# esp8266kotak.net
KiCad netlist of a schematic drawn in EAGLE
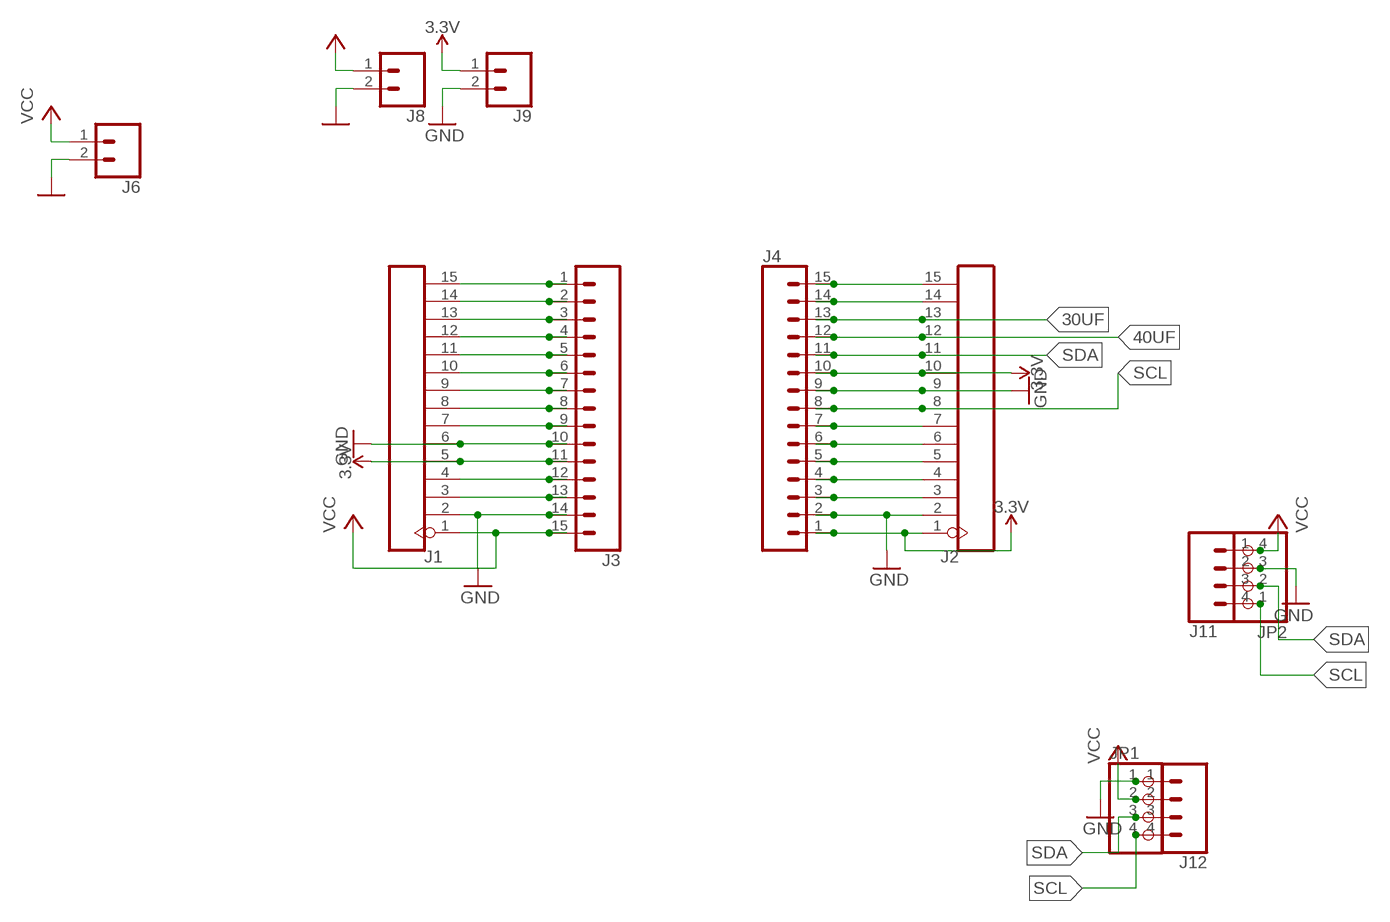
[diagram p0: schematic, sheet 1]

(export (version "E")
  (design (tool "Eeschema 10.0.6"))
  (components
    (comp (ref "J1")
      (value "HEADER-15P2.54")
      (footprint "eagle-import:15P-2.54")
      (libsource (lib "eagle-import") (part "HEADER-15P2.54"))
    )
    (comp (ref "J2")
      (value "HEADER-15P2.54")
      (footprint "eagle-import:15P-2.54")
      (libsource (lib "eagle-import") (part "HEADER-15P2.54"))
    )
    (comp (ref "J3")
      (value "CONN_15")
      (footprint "eagle-import:1X15")
      (libsource (lib "eagle-import") (part "CONN_15"))
    )
    (comp (ref "J4")
      (value "CONN_15")
      (footprint "eagle-import:1X15")
      (libsource (lib "eagle-import") (part "CONN_15"))
    )
    (comp (ref "J6")
      (value "CONN_02")
      (footprint "eagle-import:1X02")
      (libsource (lib "eagle-import") (part "CONN_02"))
    )
    (comp (ref "J8")
      (value "CONN_02")
      (footprint "eagle-import:1X02")
      (libsource (lib "eagle-import") (part "CONN_02"))
    )
    (comp (ref "J9")
      (value "CONN_02")
      (footprint "eagle-import:1X02")
      (libsource (lib "eagle-import") (part "CONN_02"))
    )
    (comp (ref "J11")
      (value "CONN_04")
      (footprint "eagle-import:1X04")
      (libsource (lib "eagle-import") (part "CONN_04"))
    )
    (comp (ref "J12")
      (value "CONN_04")
      (footprint "eagle-import:1X04")
      (libsource (lib "eagle-import") (part "CONN_04"))
    )
    (comp (ref "JP1")
      (value "PINHD-1X4/90")
      (footprint "eagle-import:1X04_90")
      (libsource (lib "eagle-import") (part "PINHD-1X4/90"))
    )
    (comp (ref "JP2")
      (value "PINHD-1X4/90")
      (footprint "eagle-import:1X04_90")
      (libsource (lib "eagle-import") (part "PINHD-1X4/90"))
    )
  )
  (nets
    (net (code "1") (name "3.3V") (class "Default")
      (node (ref "J1") (pin "5") (pinfunction "5_5") (pintype "passive"))
      (node (ref "J2") (pin "1") (pinfunction "1_1") (pintype "passive"))
      (node (ref "J2") (pin "10") (pinfunction "10_10") (pintype "passive"))
      (node (ref "J3") (pin "11") (pinfunction "11_11") (pintype "passive"))
      (node (ref "J4") (pin "1") (pinfunction "1_1") (pintype "passive"))
      (node (ref "J4") (pin "10") (pinfunction "10_10") (pintype "passive"))
      (node (ref "J9") (pin "1") (pinfunction "1_1") (pintype "passive"))
    )
    (net (code "2") (name "30UF") (class "Default")
      (node (ref "J2") (pin "13") (pinfunction "13_13") (pintype "passive"))
      (node (ref "J4") (pin "13") (pinfunction "13_13") (pintype "passive"))
    )
    (net (code "3") (name "40UF") (class "Default")
      (node (ref "J2") (pin "12") (pinfunction "12_12") (pintype "passive"))
      (node (ref "J4") (pin "12") (pinfunction "12_12") (pintype "passive"))
    )
    (net (code "4") (name "GND") (class "Default")
      (node (ref "J1") (pin "2") (pinfunction "2_2") (pintype "passive"))
      (node (ref "J1") (pin "6") (pinfunction "6_6") (pintype "passive"))
      (node (ref "J11") (pin "2") (pinfunction "2_2") (pintype "passive"))
      (node (ref "J12") (pin "1") (pinfunction "1_1") (pintype "passive"))
      (node (ref "J2") (pin "2") (pinfunction "2_2") (pintype "passive"))
      (node (ref "J2") (pin "9") (pinfunction "9_9") (pintype "passive"))
      (node (ref "J3") (pin "10") (pinfunction "10_10") (pintype "passive"))
      (node (ref "J3") (pin "14") (pinfunction "14_14") (pintype "passive"))
      (node (ref "J4") (pin "2") (pinfunction "2_2") (pintype "passive"))
      (node (ref "J4") (pin "9") (pinfunction "9_9") (pintype "passive"))
      (node (ref "J6") (pin "2") (pinfunction "2_2") (pintype "passive"))
      (node (ref "J8") (pin "2") (pinfunction "2_2") (pintype "passive"))
      (node (ref "J9") (pin "2") (pinfunction "2_2") (pintype "passive"))
      (node (ref "JP1") (pin "1") (pinfunction "1_1") (pintype "passive"))
      (node (ref "JP2") (pin "3") (pinfunction "3_3") (pintype "passive"))
    )
    (net (code "5") (name "Net-(J1-Pad3)") (class "Default")
      (node (ref "J1") (pin "3") (pinfunction "3_3") (pintype "passive"))
      (node (ref "J3") (pin "13") (pinfunction "13_13") (pintype "passive"))
    )
    (net (code "6") (name "Net-(J1-Pad4)") (class "Default")
      (node (ref "J1") (pin "4") (pinfunction "4_4") (pintype "passive"))
      (node (ref "J3") (pin "12") (pinfunction "12_12") (pintype "passive"))
    )
    (net (code "7") (name "Net-(J1-Pad7)") (class "Default")
      (node (ref "J1") (pin "7") (pinfunction "7_7") (pintype "passive"))
      (node (ref "J3") (pin "9") (pinfunction "9_9") (pintype "passive"))
    )
    (net (code "8") (name "Net-(J1-Pad8)") (class "Default")
      (node (ref "J1") (pin "8") (pinfunction "8_8") (pintype "passive"))
      (node (ref "J3") (pin "8") (pinfunction "8_8") (pintype "passive"))
    )
    (net (code "9") (name "Net-(J1-Pad9)") (class "Default")
      (node (ref "J1") (pin "9") (pinfunction "9_9") (pintype "passive"))
      (node (ref "J3") (pin "7") (pinfunction "7_7") (pintype "passive"))
    )
    (net (code "10") (name "Net-(J1-Pad10)") (class "Default")
      (node (ref "J1") (pin "10") (pinfunction "10_10") (pintype "passive"))
      (node (ref "J3") (pin "6") (pinfunction "6_6") (pintype "passive"))
    )
    (net (code "11") (name "Net-(J1-Pad11)") (class "Default")
      (node (ref "J1") (pin "11") (pinfunction "11_11") (pintype "passive"))
      (node (ref "J3") (pin "5") (pinfunction "5_5") (pintype "passive"))
    )
    (net (code "12") (name "Net-(J1-Pad12)") (class "Default")
      (node (ref "J1") (pin "12") (pinfunction "12_12") (pintype "passive"))
      (node (ref "J3") (pin "4") (pinfunction "4_4") (pintype "passive"))
    )
    (net (code "13") (name "Net-(J1-Pad13)") (class "Default")
      (node (ref "J1") (pin "13") (pinfunction "13_13") (pintype "passive"))
      (node (ref "J3") (pin "3") (pinfunction "3_3") (pintype "passive"))
    )
    (net (code "14") (name "Net-(J1-Pad14)") (class "Default")
      (node (ref "J1") (pin "14") (pinfunction "14_14") (pintype "passive"))
      (node (ref "J3") (pin "2") (pinfunction "2_2") (pintype "passive"))
    )
    (net (code "15") (name "Net-(J1-Pad15)") (class "Default")
      (node (ref "J1") (pin "15") (pinfunction "15_15") (pintype "passive"))
      (node (ref "J3") (pin "1") (pinfunction "1_1") (pintype "passive"))
    )
    (net (code "16") (name "Net-(J2-Pad3)") (class "Default")
      (node (ref "J2") (pin "3") (pinfunction "3_3") (pintype "passive"))
      (node (ref "J4") (pin "3") (pinfunction "3_3") (pintype "passive"))
    )
    (net (code "17") (name "Net-(J2-Pad4)") (class "Default")
      (node (ref "J2") (pin "4") (pinfunction "4_4") (pintype "passive"))
      (node (ref "J4") (pin "4") (pinfunction "4_4") (pintype "passive"))
    )
    (net (code "18") (name "Net-(J2-Pad5)") (class "Default")
      (node (ref "J2") (pin "5") (pinfunction "5_5") (pintype "passive"))
      (node (ref "J4") (pin "5") (pinfunction "5_5") (pintype "passive"))
    )
    (net (code "19") (name "Net-(J2-Pad6)") (class "Default")
      (node (ref "J2") (pin "6") (pinfunction "6_6") (pintype "passive"))
      (node (ref "J4") (pin "6") (pinfunction "6_6") (pintype "passive"))
    )
    (net (code "20") (name "Net-(J2-Pad7)") (class "Default")
      (node (ref "J2") (pin "7") (pinfunction "7_7") (pintype "passive"))
      (node (ref "J4") (pin "7") (pinfunction "7_7") (pintype "passive"))
    )
    (net (code "21") (name "Net-(J2-Pad14)") (class "Default")
      (node (ref "J2") (pin "14") (pinfunction "14_14") (pintype "passive"))
      (node (ref "J4") (pin "14") (pinfunction "14_14") (pintype "passive"))
    )
    (net (code "22") (name "Net-(J2-Pad15)") (class "Default")
      (node (ref "J2") (pin "15") (pinfunction "15_15") (pintype "passive"))
      (node (ref "J4") (pin "15") (pinfunction "15_15") (pintype "passive"))
    )
    (net (code "23") (name "SCL") (class "Default")
      (node (ref "J11") (pin "4") (pinfunction "4_4") (pintype "passive"))
      (node (ref "J12") (pin "4") (pinfunction "4_4") (pintype "passive"))
      (node (ref "J2") (pin "8") (pinfunction "8_8") (pintype "passive"))
      (node (ref "J4") (pin "8") (pinfunction "8_8") (pintype "passive"))
      (node (ref "JP1") (pin "4") (pinfunction "4_4") (pintype "passive"))
      (node (ref "JP2") (pin "1") (pinfunction "1_1") (pintype "passive"))
    )
    (net (code "24") (name "SDA") (class "Default")
      (node (ref "J11") (pin "3") (pinfunction "3_3") (pintype "passive"))
      (node (ref "J12") (pin "3") (pinfunction "3_3") (pintype "passive"))
      (node (ref "J2") (pin "11") (pinfunction "11_11") (pintype "passive"))
      (node (ref "J4") (pin "11") (pinfunction "11_11") (pintype "passive"))
      (node (ref "JP1") (pin "3") (pinfunction "3_3") (pintype "passive"))
      (node (ref "JP2") (pin "2") (pinfunction "2_2") (pintype "passive"))
    )
    (net (code "25") (name "VCC") (class "Default")
      (node (ref "J1") (pin "1") (pinfunction "1_1") (pintype "passive"))
      (node (ref "J11") (pin "1") (pinfunction "1_1") (pintype "passive"))
      (node (ref "J12") (pin "2") (pinfunction "2_2") (pintype "passive"))
      (node (ref "J3") (pin "15") (pinfunction "15_15") (pintype "passive"))
      (node (ref "J6") (pin "1") (pinfunction "1_1") (pintype "passive"))
      (node (ref "J8") (pin "1") (pinfunction "1_1") (pintype "passive"))
      (node (ref "JP1") (pin "2") (pinfunction "2_2") (pintype "passive"))
      (node (ref "JP2") (pin "4") (pinfunction "4_4") (pintype "passive"))
    )
  )
)
